# Adafruit_Feather_M4_Express_CAN.net
KiCad netlist of a schematic drawn in EAGLE
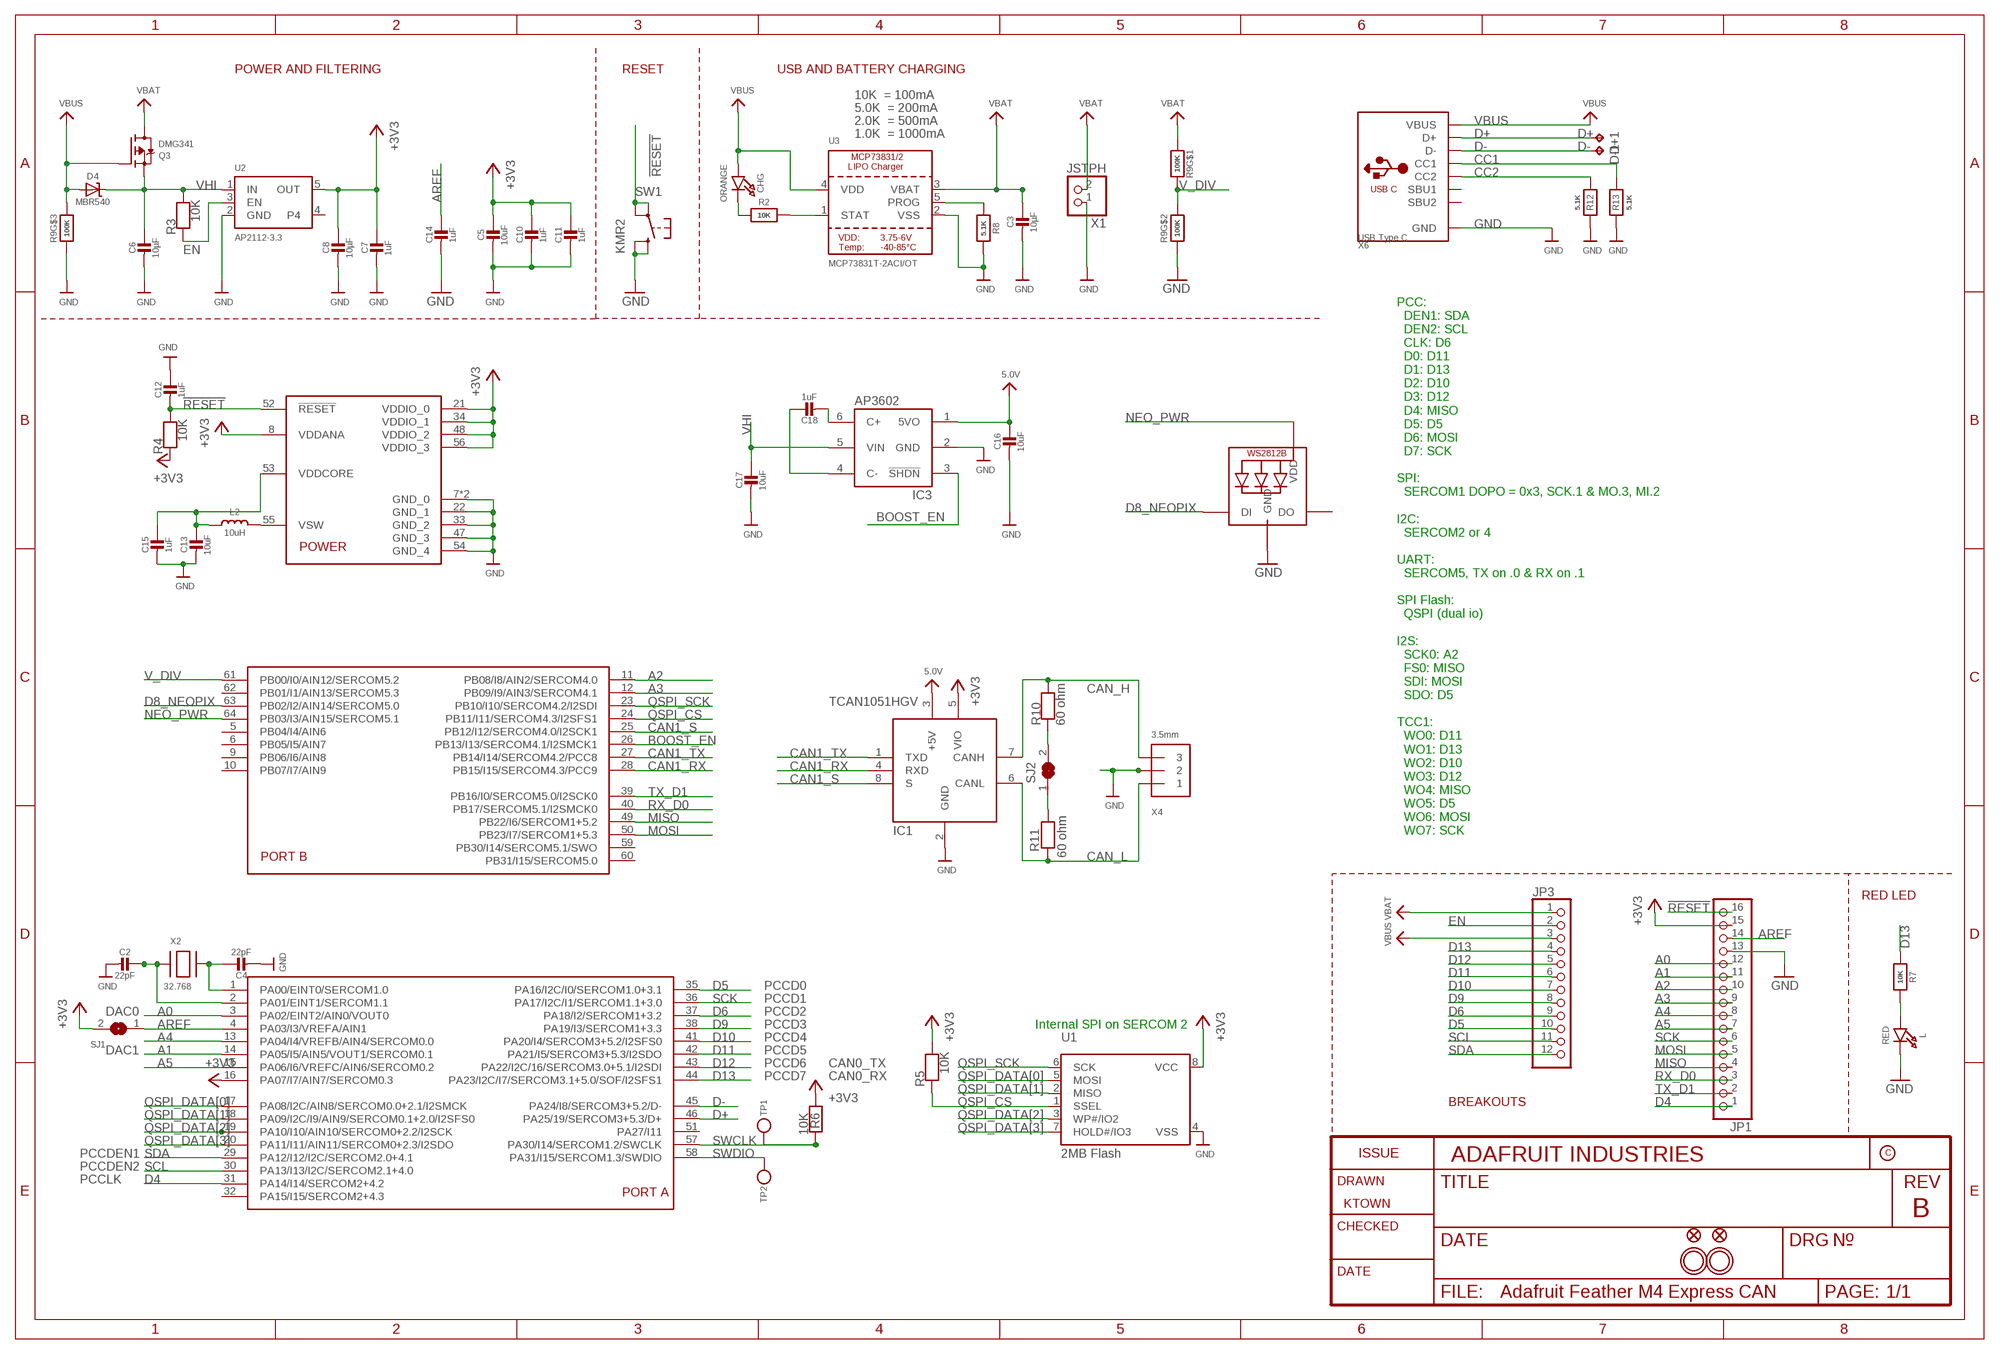
[diagram p0: schematic, sheet 1]

(export (version "E")
  (design (tool "Eeschema 10.0.6"))
  (components
    (comp (ref "C2")
      (value "22pF")
      (footprint "eagle-import:0603-NO")
      (libsource (lib "eagle-import") (part "CAP_CERAMIC0603_NO"))
    )
    (comp (ref "C3")
      (value "10µF")
      (footprint "eagle-import:0805-NO")
      (libsource (lib "eagle-import") (part "CAP_CERAMIC0805-NOOUTLINE"))
    )
    (comp (ref "C4")
      (value "22pF")
      (footprint "eagle-import:0603-NO")
      (libsource (lib "eagle-import") (part "CAP_CERAMIC0603_NO"))
    )
    (comp (ref "C5")
      (value "10uF")
      (footprint "eagle-import:0805-NO")
      (libsource (lib "eagle-import") (part "CAP_CERAMIC0805-NOOUTLINE"))
    )
    (comp (ref "C6")
      (value "10µF")
      (footprint "eagle-import:0805-NO")
      (libsource (lib "eagle-import") (part "CAP_CERAMIC0805-NOOUTLINE"))
    )
    (comp (ref "C7")
      (value "1uF")
      (footprint "eagle-import:0603-NO")
      (libsource (lib "eagle-import") (part "CAP_CERAMIC0603_NO"))
    )
    (comp (ref "C8")
      (value "10µF")
      (footprint "eagle-import:0805-NO")
      (fields (field (name "REV") "C"))
      (libsource (lib "eagle-import") (part "CAP_CERAMIC0805-NOOUTLINE"))
    )
    (comp (ref "C10")
      (value "1uF")
      (footprint "eagle-import:0603-NO")
      (libsource (lib "eagle-import") (part "CAP_CERAMIC0603_NO"))
    )
    (comp (ref "C11")
      (value "1uF")
      (footprint "eagle-import:0603-NO")
      (libsource (lib "eagle-import") (part "CAP_CERAMIC0603_NO"))
    )
    (comp (ref "C12")
      (value "1uF")
      (footprint "eagle-import:0603-NO")
      (libsource (lib "eagle-import") (part "CAP_CERAMIC0603_NO"))
    )
    (comp (ref "C13")
      (value "10uF")
      (footprint "eagle-import:0805-NO")
      (libsource (lib "eagle-import") (part "CAP_CERAMIC0805-NOOUTLINE"))
    )
    (comp (ref "C14")
      (value "1uF")
      (footprint "eagle-import:0603-NO")
      (libsource (lib "eagle-import") (part "CAP_CERAMIC0603_NO"))
    )
    (comp (ref "C15")
      (value "1uF")
      (footprint "eagle-import:0603-NO")
      (libsource (lib "eagle-import") (part "CAP_CERAMIC0603_NO"))
    )
    (comp (ref "C16")
      (value "10uF")
      (footprint "eagle-import:_0805MP")
      (libsource (lib "eagle-import") (part "CAP_CERAMIC_0805MP"))
    )
    (comp (ref "C17")
      (value "10uF")
      (footprint "eagle-import:0805-NO")
      (libsource (lib "eagle-import") (part "CAP_CERAMIC0805-NOOUTLINE"))
    )
    (comp (ref "C18")
      (value "1uF")
      (footprint "eagle-import:0805_10MGAP")
      (libsource (lib "eagle-import") (part "CAP_CERAMIC0805_10MGAP"))
    )
    (comp (ref "CHG")
      (value "ORANGE")
      (footprint "eagle-import:CHIPLED_0603_NOOUTLINE")
      (libsource (lib "eagle-import") (part "LED0603_NOOUTLINE"))
    )
    (comp (ref "D+1")
      (value "TPB1,27")
      (footprint "eagle-import:B1,27")
      (libsource (lib "eagle-import") (part "TPB1,27"))
    )
    (comp (ref "D-1")
      (value "TPB1,27")
      (footprint "eagle-import:B1,27")
      (libsource (lib "eagle-import") (part "TPB1,27"))
    )
    (comp (ref "D4")
      (value "MBR540")
      (footprint "eagle-import:SOD-123")
      (libsource (lib "eagle-import") (part "DIODE-SCHOTTKYSOD-123"))
    )
    (comp (ref "IC1")
      (value "TCAN1051HGV")
      (footprint "eagle-import:SOIC8_150MIL")
      (libsource (lib "eagle-import") (part "CAN_TRANSCIEVER_TCAN1051V"))
    )
    (comp (ref "IC3")
      (value "AP3602")
      (footprint "eagle-import:SOT23-6")
      (libsource (lib "eagle-import") (part "AP3602"))
    )
    (comp (ref "JP1")
      (value "HEADER-1X16ROUND")
      (footprint "eagle-import:1X16_ROUND")
      (libsource (lib "eagle-import") (part "HEADER-1X16ROUND"))
    )
    (comp (ref "JP3")
      (value "HEADER-1X12")
      (footprint "eagle-import:1X12_ROUND")
      (libsource (lib "eagle-import") (part "HEADER-1X12"))
    )
    (comp (ref "L")
      (value "RED")
      (footprint "eagle-import:CHIPLED_0603_NOOUTLINE")
      (libsource (lib "eagle-import") (part "LED0603_NOOUTLINE"))
    )
    (comp (ref "L2")
      (value "10uH")
      (footprint "eagle-import:INDUCTOR_1007")
      (libsource (lib "eagle-import") (part "INDUCTOR"))
    )
    (comp (ref "LED1")
      (value "WS2812B3535")
      (footprint "eagle-import:LED3535")
      (libsource (lib "eagle-import") (part "WS2812B3535"))
    )
    (comp (ref "Q3")
      (value "DMG341")
      (footprint "eagle-import:SOT23-R")
      (libsource (lib "eagle-import") (part "MOSFET-P"))
    )
    (comp (ref "R2")
      (value "10K")
      (footprint "eagle-import:0603-NO")
      (libsource (lib "eagle-import") (part "RESISTOR_0603_NOOUT"))
    )
    (comp (ref "R3")
      (value "10K")
      (footprint "eagle-import:0603-NO")
      (libsource (lib "eagle-import") (part "RESISTOR_0603_NOOUT"))
    )
    (comp (ref "R4")
      (value "10K")
      (footprint "eagle-import:0603-NO")
      (libsource (lib "eagle-import") (part "RESISTOR_0603_NOOUT"))
    )
    (comp (ref "R5")
      (value "10K")
      (footprint "eagle-import:0603-NO")
      (libsource (lib "eagle-import") (part "RESISTOR_0603_NOOUT"))
    )
    (comp (ref "R6")
      (value "10K")
      (footprint "eagle-import:0603-NO")
      (libsource (lib "eagle-import") (part "RESISTOR_0603_NOOUT"))
    )
    (comp (ref "R7")
      (value "10K")
      (footprint "eagle-import:0603-NO")
      (libsource (lib "eagle-import") (part "RESISTOR_0603_NOOUT"))
    )
    (comp (ref "R8")
      (value "5.1K")
      (footprint "eagle-import:0603-NO")
      (libsource (lib "eagle-import") (part "RESISTOR_0603_NOOUT"))
    )
    (comp (ref "R9")
      (value "100K")
      (footprint "eagle-import:RESPACK_4X0603_NO")
      (libsource (lib "eagle-import") (part "RESISTOR_4PACK_NO"))
    )
    (comp (ref "R10")
      (value "60 ohm")
      (footprint "eagle-import:0805-NO")
      (libsource (lib "eagle-import") (part "RESISTOR0805_NOOUTLINE"))
    )
    (comp (ref "R11")
      (value "60 ohm")
      (footprint "eagle-import:0805-NO")
      (libsource (lib "eagle-import") (part "RESISTOR0805_NOOUTLINE"))
    )
    (comp (ref "R12")
      (value "5.1K")
      (footprint "eagle-import:0603-NO")
      (libsource (lib "eagle-import") (part "RESISTOR_0603_NOOUT"))
    )
    (comp (ref "R13")
      (value "5.1K")
      (footprint "eagle-import:0603-NO")
      (libsource (lib "eagle-import") (part "RESISTOR_0603_NOOUT"))
    )
    (comp (ref "SJ1")
      (value "SOLDERJUMPERCLOSED")
      (footprint "eagle-import:SOLDERJUMPER_CLOSEDWIRE")
      (libsource (lib "eagle-import") (part "SOLDERJUMPERCLOSED"))
    )
    (comp (ref "SJ2")
      (value "SOLDERJUMPER_CLOSED")
      (footprint "eagle-import:SOLDERJUMPER_CLOSEDWIRE")
      (libsource (lib "eagle-import") (part "SOLDERJUMPER_CLOSED"))
    )
    (comp (ref "SW1")
      (value "KMR2")
      (footprint "eagle-import:BTN_KMR2_4.6X2.8")
      (libsource (lib "eagle-import") (part "SWITCH_TACT_SMT4.6X2.8"))
    )
    (comp (ref "TP1")
      (value "TESTPOINTROUND1.5MM")
      (footprint "eagle-import:TESTPOINT_ROUND_1.5MM")
      (libsource (lib "eagle-import") (part "TESTPOINTROUND1.5MM"))
    )
    (comp (ref "TP2")
      (value "TESTPOINTROUND1.5MM")
      (footprint "eagle-import:TESTPOINT_ROUND_1.5MM")
      (libsource (lib "eagle-import") (part "TESTPOINTROUND1.5MM"))
    )
    (comp (ref "U$14")
      (value "ATSAMD51J")
      (footprint "eagle-import:PQFN64-1")
      (libsource (lib "eagle-import") (part "ATSAMD51J"))
    )
    (comp (ref "U$31")
      (value "MOUNTINGHOLE2.5")
      (footprint "eagle-import:MOUNTINGHOLE_2.5_PLATED")
      (libsource (lib "eagle-import") (part "MOUNTINGHOLE2.5"))
    )
    (comp (ref "U$32")
      (value "MOUNTINGHOLE2.5")
      (footprint "eagle-import:MOUNTINGHOLE_2.5_PLATED")
      (libsource (lib "eagle-import") (part "MOUNTINGHOLE2.5"))
    )
    (comp (ref "U$34")
      (value "FIDUCIAL_1MM")
      (footprint "eagle-import:FIDUCIAL_1MM")
      (libsource (lib "eagle-import") (part "FIDUCIAL_1MM"))
    )
    (comp (ref "U$35")
      (value "FIDUCIAL_1MM")
      (footprint "eagle-import:FIDUCIAL_1MM")
      (libsource (lib "eagle-import") (part "FIDUCIAL_1MM"))
    )
    (comp (ref "U1")
      (value "2MB Flash")
      (footprint "eagle-import:USON8")
      (libsource (lib "eagle-import") (part "SPIFLASH_8PINUX"))
    )
    (comp (ref "U2")
      (value "AP2112-3.3")
      (footprint "eagle-import:SOT23-5@1")
      (libsource (lib "eagle-import") (part "VREG_SOT23-5"))
    )
    (comp (ref "U3")
      (value "MCP73831T-2ACI/OT")
      (footprint "eagle-import:SOT23-5")
      (libsource (lib "eagle-import") (part "MCP73831/2"))
    )
    (comp (ref "X1")
      (value "JSTPH")
      (footprint "eagle-import:JSTPH2_BATT")
      (libsource (lib "eagle-import") (part "CON_JST_PH_2PIN_BATT"))
    )
    (comp (ref "X2")
      (value "32.768")
      (footprint "eagle-import:XTAL3215")
      (libsource (lib "eagle-import") (part "XTAL-3.2X1.5"))
    )
    (comp (ref "X4")
      (value "3.5mm")
      (footprint "eagle-import:TERMBLOCK_1X3-3.5MM")
      (libsource (lib "eagle-import") (part "TERMBLOCK_1X3"))
    )
    (comp (ref "X6")
      (value "USB Type C")
      (footprint "eagle-import:USB_C_CUSB31-CFM2AX-01-X")
      (libsource (lib "eagle-import") (part "USB_C"))
    )
  )
  (nets
    (net (code "1") (name "+3V3") (class "Default")
      (node (ref "C10") (pin "1") (pinfunction "1_1") (pintype "passive"))
      (node (ref "C11") (pin "1") (pinfunction "1_1") (pintype "passive"))
      (node (ref "C5") (pin "1") (pinfunction "1_1") (pintype "passive"))
      (node (ref "C7") (pin "1") (pinfunction "1_1") (pintype "passive"))
      (node (ref "C8") (pin "1") (pinfunction "1_1") (pintype "passive"))
      (node (ref "IC1") (pin "5") (pinfunction "VIO_5") (pintype "power_in"))
      (node (ref "JP1") (pin "15") (pinfunction "15_15") (pintype "passive"))
      (node (ref "R4") (pin "1") (pinfunction "1_1") (pintype "passive"))
      (node (ref "R5") (pin "2") (pinfunction "2_2") (pintype "passive"))
      (node (ref "R6") (pin "1") (pinfunction "1_1") (pintype "passive"))
      (node (ref "SJ1") (pin "2") (pinfunction "2_2") (pintype "passive"))
      (node (ref "U$14") (pin "16") (pinfunction "PA07/I7/AIN7/SERCOM0.3_16") (pintype "bidirectional"))
      (node (ref "U$14") (pin "21") (pinfunction "VDDIO_0_21") (pintype "bidirectional"))
      (node (ref "U$14") (pin "34") (pinfunction "VDDIO_1_34") (pintype "bidirectional"))
      (node (ref "U$14") (pin "48") (pinfunction "VDDIO_2_48") (pintype "bidirectional"))
      (node (ref "U$14") (pin "56") (pinfunction "VDDIO_3_56") (pintype "bidirectional"))
      (node (ref "U$14") (pin "8") (pinfunction "VDDANA_8") (pintype "bidirectional"))
      (node (ref "U1") (pin "8") (pinfunction "VCC_8") (pintype "bidirectional"))
      (node (ref "U2") (pin "5") (pinfunction "OUT_5") (pintype "power_in"))
    )
    (net (code "2") (name "/A0") (class "Default")
      (node (ref "JP1") (pin "12") (pinfunction "12_12") (pintype "passive"))
      (node (ref "U$14") (pin "3") (pinfunction "PA02/EINT2/AIN0/VOUT0_3") (pintype "bidirectional"))
    )
    (net (code "3") (name "/A1") (class "Default")
      (node (ref "JP1") (pin "11") (pinfunction "11_11") (pintype "passive"))
      (node (ref "U$14") (pin "14") (pinfunction "PA05/I5/AIN5/VOUT1/SERCOM0.1_14") (pintype "bidirectional"))
    )
    (net (code "4") (name "/A2") (class "Default")
      (node (ref "JP1") (pin "10") (pinfunction "10_10") (pintype "passive"))
      (node (ref "U$14") (pin "11") (pinfunction "PB08/I8/AIN2/SERCOM4.0_11") (pintype "bidirectional"))
    )
    (net (code "5") (name "/A3") (class "Default")
      (node (ref "JP1") (pin "9") (pinfunction "9_9") (pintype "passive"))
      (node (ref "U$14") (pin "12") (pinfunction "PB09/I9/AIN3/SERCOM4.1_12") (pintype "bidirectional"))
    )
    (net (code "6") (name "/A4") (class "Default")
      (node (ref "JP1") (pin "8") (pinfunction "8_8") (pintype "passive"))
      (node (ref "U$14") (pin "13") (pinfunction "PA04/I4/VREFB/AIN4/SERCOM0.0_13") (pintype "bidirectional"))
    )
    (net (code "7") (name "/A5") (class "Default")
      (node (ref "JP1") (pin "7") (pinfunction "7_7") (pintype "passive"))
      (node (ref "U$14") (pin "15") (pinfunction "PA06/I6/VREFC/AIN6/SERCOM0.2_15") (pintype "bidirectional"))
    )
    (net (code "8") (name "/AREF") (class "Default")
      (node (ref "C14") (pin "1") (pinfunction "1_1") (pintype "passive"))
      (node (ref "JP1") (pin "14") (pinfunction "14_14") (pintype "passive"))
      (node (ref "SJ1") (pin "1") (pinfunction "1_1") (pintype "passive"))
      (node (ref "U$14") (pin "4") (pinfunction "PA03/I3/VREFA/AIN1_4") (pintype "bidirectional"))
    )
    (net (code "9") (name "/BOOST_EN") (class "Default")
      (node (ref "IC3") (pin "3") (pinfunction "~{SHDN}_3") (pintype "input"))
      (node (ref "U$14") (pin "26") (pinfunction "PB13/I13/SERCOM4.1/I2SMCK1_26") (pintype "bidirectional"))
    )
    (net (code "10") (name "/CAN1_RX") (class "Default")
      (node (ref "IC1") (pin "4") (pinfunction "RXD_4") (pintype "output"))
      (node (ref "U$14") (pin "28") (pinfunction "PB15/I15/SERCOM4.3/PCC9_28") (pintype "bidirectional"))
    )
    (net (code "11") (name "/CAN1_S") (class "Default")
      (node (ref "IC1") (pin "8") (pinfunction "S_8") (pintype "input"))
      (node (ref "U$14") (pin "25") (pinfunction "PB12/I12/SERCOM4.0/I2SCK1_25") (pintype "bidirectional"))
    )
    (net (code "12") (name "/CAN1_TX") (class "Default")
      (node (ref "IC1") (pin "1") (pinfunction "TXD_1") (pintype "input"))
      (node (ref "U$14") (pin "27") (pinfunction "PB14/I14/SERCOM4.2/PCC8_27") (pintype "bidirectional"))
    )
    (net (code "13") (name "/CAN_H") (class "Default")
      (node (ref "IC1") (pin "7") (pinfunction "CANH_7") (pintype "bidirectional"))
      (node (ref "R10") (pin "2") (pinfunction "2_2") (pintype "passive"))
      (node (ref "X4") (pin "3") (pinfunction "3_3") (pintype "passive"))
    )
    (net (code "14") (name "/CAN_L") (class "Default")
      (node (ref "IC1") (pin "6") (pinfunction "CANL_6") (pintype "bidirectional"))
      (node (ref "R11") (pin "2") (pinfunction "2_2") (pintype "passive"))
      (node (ref "X4") (pin "1") (pinfunction "1_1") (pintype "passive"))
    )
    (net (code "15") (name "/CC1") (class "Default")
      (node (ref "R13") (pin "2") (pinfunction "2_2") (pintype "passive"))
      (node (ref "X6") (pin "A5") (pinfunction "CC1_A5") (pintype "bidirectional"))
    )
    (net (code "16") (name "/CC2") (class "Default")
      (node (ref "R12") (pin "2") (pinfunction "2_2") (pintype "passive"))
      (node (ref "X6") (pin "B5") (pinfunction "CC2_B5") (pintype "bidirectional"))
    )
    (net (code "17") (name "/D+") (class "Default")
      (node (ref "D+1") (pin "TP") (pinfunction "TP_TP") (pintype "input"))
      (node (ref "U$14") (pin "46") (pinfunction "PA25/19/SERCOM3+5.3/D+_46") (pintype "bidirectional"))
      (node (ref "X6") (pin "A6") (pinfunction "D+_A6") (pintype "bidirectional"))
      (node (ref "X6") (pin "B6") (pinfunction "D+_B6") (pintype "bidirectional"))
    )
    (net (code "18") (name "/D-") (class "Default")
      (node (ref "D-1") (pin "TP") (pinfunction "TP_TP") (pintype "input"))
      (node (ref "U$14") (pin "45") (pinfunction "PA24/I8/SERCOM3+5.2/D-_45") (pintype "bidirectional"))
      (node (ref "X6") (pin "A7") (pinfunction "D-_A7") (pintype "bidirectional"))
      (node (ref "X6") (pin "B7") (pinfunction "D-_B7") (pintype "bidirectional"))
    )
    (net (code "19") (name "/D4") (class "Default")
      (node (ref "JP1") (pin "1") (pinfunction "1_1") (pintype "passive"))
      (node (ref "U$14") (pin "31") (pinfunction "PA14/I14/SERCOM2+4.2_31") (pintype "bidirectional"))
    )
    (net (code "20") (name "/D5") (class "Default")
      (node (ref "JP3") (pin "10") (pinfunction "10_10") (pintype "passive"))
      (node (ref "U$14") (pin "35") (pinfunction "PA16/I2C/I0/SERCOM1.0+3.1_35") (pintype "bidirectional"))
    )
    (net (code "21") (name "/D6") (class "Default")
      (node (ref "JP3") (pin "9") (pinfunction "9_9") (pintype "passive"))
      (node (ref "U$14") (pin "37") (pinfunction "PA18/I2/SERCOM1+3.2_37") (pintype "bidirectional"))
    )
    (net (code "22") (name "/D8_NEOPIX") (class "Default")
      (node (ref "LED1") (pin "1") (pinfunction "DI_1") (pintype "input"))
      (node (ref "U$14") (pin "63") (pinfunction "PB02/I2/AIN14/SERCOM5.0_63") (pintype "bidirectional"))
    )
    (net (code "23") (name "/D9") (class "Default")
      (node (ref "JP3") (pin "8") (pinfunction "8_8") (pintype "passive"))
      (node (ref "U$14") (pin "38") (pinfunction "PA19/I3/SERCOM1+3.3_38") (pintype "bidirectional"))
    )
    (net (code "24") (name "/D10") (class "Default")
      (node (ref "JP3") (pin "7") (pinfunction "7_7") (pintype "passive"))
      (node (ref "U$14") (pin "41") (pinfunction "PA20/I4/SERCOM3+5.2/I2SFS0_41") (pintype "bidirectional"))
    )
    (net (code "25") (name "/D11") (class "Default")
      (node (ref "JP3") (pin "6") (pinfunction "6_6") (pintype "passive"))
      (node (ref "U$14") (pin "42") (pinfunction "PA21/I5/SERCOM3+5.3/I2SDO_42") (pintype "bidirectional"))
    )
    (net (code "26") (name "/D12") (class "Default")
      (node (ref "JP3") (pin "5") (pinfunction "5_5") (pintype "passive"))
      (node (ref "U$14") (pin "43") (pinfunction "PA22/I2C/16/SERCOM3.0+5.1/I2SDI_43") (pintype "bidirectional"))
    )
    (net (code "27") (name "/D13") (class "Default")
      (node (ref "JP3") (pin "4") (pinfunction "4_4") (pintype "passive"))
      (node (ref "R7") (pin "1") (pinfunction "1_1") (pintype "passive"))
      (node (ref "U$14") (pin "44") (pinfunction "PA23/I2C/I7/SERCOM3.1+5.0/SOF/I2SFS1_44") (pintype "bidirectional"))
    )
    (net (code "28") (name "/EN") (class "Default")
      (node (ref "JP3") (pin "2") (pinfunction "2_2") (pintype "passive"))
      (node (ref "R3") (pin "1") (pinfunction "1_1") (pintype "passive"))
      (node (ref "U2") (pin "3") (pinfunction "EN_3") (pintype "input"))
    )
    (net (code "29") (name "/MISO") (class "Default")
      (node (ref "JP1") (pin "4") (pinfunction "4_4") (pintype "passive"))
      (node (ref "U$14") (pin "49") (pinfunction "PB22/I6/SERCOM1+5.2_49") (pintype "bidirectional"))
    )
    (net (code "30") (name "/MOSI") (class "Default")
      (node (ref "JP1") (pin "5") (pinfunction "5_5") (pintype "passive"))
      (node (ref "U$14") (pin "50") (pinfunction "PB23/I7/SERCOM1+5.3_50") (pintype "bidirectional"))
    )
    (net (code "31") (name "/NEO_PWR") (class "Default")
      (node (ref "LED1") (pin "2") (pinfunction "VDD_2") (pintype "power_in"))
      (node (ref "U$14") (pin "64") (pinfunction "PB03/I3/AIN15/SERCOM5.1_64") (pintype "bidirectional"))
    )
    (net (code "32") (name "/QSPI_CS") (class "Default")
      (node (ref "R5") (pin "1") (pinfunction "1_1") (pintype "passive"))
      (node (ref "U$14") (pin "24") (pinfunction "PB11/I11/SERCOM4.3/I2SFS1_24") (pintype "bidirectional"))
      (node (ref "U1") (pin "1") (pinfunction "SSEL_1") (pintype "bidirectional"))
    )
    (net (code "33") (name "/QSPI_DATA[0]") (class "Default")
      (node (ref "U$14") (pin "17") (pinfunction "PA08/I2C/AIN8/SERCOM0.0+2.1/I2SMCK_17") (pintype "bidirectional"))
      (node (ref "U1") (pin "5") (pinfunction "MOSI_5") (pintype "bidirectional"))
    )
    (net (code "34") (name "/QSPI_DATA[1]") (class "Default")
      (node (ref "U$14") (pin "18") (pinfunction "PA09/I2C/I9/AIN9/SERCOM0.1+2.0/I2SFS0_18") (pintype "bidirectional"))
      (node (ref "U1") (pin "2") (pinfunction "MISO_2") (pintype "bidirectional"))
    )
    (net (code "35") (name "/QSPI_DATA[2]") (class "Default")
      (node (ref "U$14") (pin "19") (pinfunction "PA10/I10/AIN10/SERCOM0+2.2/I2SCK_19") (pintype "bidirectional"))
      (node (ref "U1") (pin "3") (pinfunction "WP#/IO2_3") (pintype "bidirectional"))
    )
    (net (code "36") (name "/QSPI_DATA[3]") (class "Default")
      (node (ref "U$14") (pin "20") (pinfunction "PA11/I11/AIN11/SERCOM0+2.3/I2SDO_20") (pintype "bidirectional"))
      (node (ref "U1") (pin "7") (pinfunction "HOLD#/IO3_7") (pintype "bidirectional"))
    )
    (net (code "37") (name "/QSPI_SCK") (class "Default")
      (node (ref "U$14") (pin "23") (pinfunction "PB10/I10/SERCOM4.2/I2SDI_23") (pintype "bidirectional"))
      (node (ref "U1") (pin "6") (pinfunction "SCK_6") (pintype "bidirectional"))
    )
    (net (code "38") (name "/RX_D0") (class "Default")
      (node (ref "JP1") (pin "3") (pinfunction "3_3") (pintype "passive"))
      (node (ref "U$14") (pin "40") (pinfunction "PB17/SERCOM5.1/I2SMCK0_40") (pintype "bidirectional"))
    )
    (net (code "39") (name "/SCK") (class "Default")
      (node (ref "JP1") (pin "6") (pinfunction "6_6") (pintype "passive"))
      (node (ref "U$14") (pin "36") (pinfunction "PA17/I2C/I1/SERCOM1.1+3.0_36") (pintype "bidirectional"))
    )
    (net (code "40") (name "/SCL") (class "Default")
      (node (ref "JP3") (pin "11") (pinfunction "11_11") (pintype "passive"))
      (node (ref "U$14") (pin "30") (pinfunction "PA13/I13/I2C/SERCOM2.1+4.0_30") (pintype "bidirectional"))
    )
    (net (code "41") (name "/SDA") (class "Default")
      (node (ref "JP3") (pin "12") (pinfunction "12_12") (pintype "passive"))
      (node (ref "U$14") (pin "29") (pinfunction "PA12/I12/I2C/SERCOM2.0+4.1_29") (pintype "bidirectional"))
    )
    (net (code "42") (name "/SWCLK") (class "Default")
      (node (ref "R6") (pin "2") (pinfunction "2_2") (pintype "passive"))
      (node (ref "TP1") (pin "P$1") (pinfunction "P$1_P$1") (pintype "bidirectional"))
      (node (ref "U$14") (pin "57") (pinfunction "PA30/I14/SERCOM1.2/SWCLK_57") (pintype "bidirectional"))
    )
    (net (code "43") (name "/SWDIO") (class "Default")
      (node (ref "TP2") (pin "P$1") (pinfunction "P$1_P$1") (pintype "bidirectional"))
      (node (ref "U$14") (pin "58") (pinfunction "PA31/I15/SERCOM1.3/SWDIO_58") (pintype "bidirectional"))
    )
    (net (code "44") (name "/TX_D1") (class "Default")
      (node (ref "JP1") (pin "2") (pinfunction "2_2") (pintype "passive"))
      (node (ref "U$14") (pin "39") (pinfunction "PB16/I0/SERCOM5.0/I2SCK0_39") (pintype "bidirectional"))
    )
    (net (code "45") (name "/VHI") (class "Default")
      (node (ref "C17") (pin "1") (pinfunction "1_1") (pintype "passive"))
      (node (ref "C6") (pin "1") (pinfunction "1_1") (pintype "passive"))
      (node (ref "D4") (pin "C") (pinfunction "C_C") (pintype "passive"))
      (node (ref "IC3") (pin "5") (pinfunction "VIN_5") (pintype "power_in"))
      (node (ref "Q3") (pin "2") (pinfunction "S_2") (pintype "passive"))
      (node (ref "R3") (pin "2") (pinfunction "2_2") (pintype "passive"))
      (node (ref "U2") (pin "1") (pinfunction "IN_1") (pintype "power_in"))
    )
    (net (code "46") (name "/V_DIV") (class "Default")
      (node (ref "R9") (pin "1") (pinfunction "1_1") (pintype "passive"))
      (node (ref "R9") (pin "2") (pinfunction "1_2") (pintype "passive"))
      (node (ref "U$14") (pin "61") (pinfunction "PB00/I0/AIN12/SERCOM5.2_61") (pintype "bidirectional"))
    )
    (net (code "47") (name "/~{RESET}") (class "Default")
      (node (ref "C12") (pin "2") (pinfunction "2_2") (pintype "passive"))
      (node (ref "JP1") (pin "16") (pinfunction "16_16") (pintype "passive"))
      (node (ref "R4") (pin "2") (pinfunction "2_2") (pintype "passive"))
      (node (ref "SW1") (pin "A") (pinfunction "P_A") (pintype "passive"))
      (node (ref "SW1") (pin "A'") (pinfunction "P1_A'") (pintype "passive"))
      (node (ref "U$14") (pin "52") (pinfunction "~{RESET}_52") (pintype "bidirectional"))
    )
    (net (code "48") (name "5.0V") (class "Default")
      (node (ref "C16") (pin "1") (pinfunction "1_1") (pintype "passive"))
      (node (ref "IC1") (pin "3") (pinfunction "+5V_3") (pintype "power_in"))
      (node (ref "IC3") (pin "1") (pinfunction "5VO_1") (pintype "power_in"))
    )
    (net (code "49") (name "GND") (class "Default")
      (node (ref "C10") (pin "2") (pinfunction "2_2") (pintype "passive"))
      (node (ref "C11") (pin "2") (pinfunction "2_2") (pintype "passive"))
      (node (ref "C12") (pin "1") (pinfunction "1_1") (pintype "passive"))
      (node (ref "C13") (pin "2") (pinfunction "2_2") (pintype "passive"))
      (node (ref "C14") (pin "2") (pinfunction "2_2") (pintype "passive"))
      (node (ref "C15") (pin "2") (pinfunction "2_2") (pintype "passive"))
      (node (ref "C16") (pin "2") (pinfunction "2_2") (pintype "passive"))
      (node (ref "C17") (pin "2") (pinfunction "2_2") (pintype "passive"))
      (node (ref "C2") (pin "2") (pinfunction "2_2") (pintype "passive"))
      (node (ref "C3") (pin "2") (pinfunction "2_2") (pintype "passive"))
      (node (ref "C4") (pin "2") (pinfunction "2_2") (pintype "passive"))
      (node (ref "C5") (pin "2") (pinfunction "2_2") (pintype "passive"))
      (node (ref "C6") (pin "2") (pinfunction "2_2") (pintype "passive"))
      (node (ref "C7") (pin "2") (pinfunction "2_2") (pintype "passive"))
      (node (ref "C8") (pin "2") (pinfunction "2_2") (pintype "passive"))
      (node (ref "IC1") (pin "2") (pinfunction "GND_2") (pintype "power_in"))
      (node (ref "IC3") (pin "2") (pinfunction "GND_2") (pintype "power_in"))
      (node (ref "JP1") (pin "13") (pinfunction "13_13") (pintype "passive"))
      (node (ref "L") (pin "C") (pinfunction "C_C") (pintype "passive"))
      (node (ref "LED1") (pin "4") (pinfunction "GND_4") (pintype "power_in"))
      (node (ref "R12") (pin "1") (pinfunction "1_1") (pintype "passive"))
      (node (ref "R13") (pin "1") (pinfunction "1_1") (pintype "passive"))
      (node (ref "R8") (pin "2") (pinfunction "2_2") (pintype "passive"))
      (node (ref "R9") (pin "3") (pinfunction "1_3") (pintype "passive"))
      (node (ref "R9") (pin "7") (pinfunction "2_7") (pintype "passive"))
      (node (ref "SW1") (pin "B") (pinfunction "S_B") (pintype "passive"))
      (node (ref "SW1") (pin "B'") (pinfunction "S1_B'") (pintype "passive"))
      (node (ref "U$14") (pin "22") (pinfunction "GND_1_22") (pintype "bidirectional"))
      (node (ref "U$14") (pin "33") (pinfunction "GND_2_33") (pintype "bidirectional"))
      (node (ref "U$14") (pin "47") (pinfunction "GND_3_47") (pintype "bidirectional"))
      (node (ref "U$14") (pin "54") (pinfunction "GND_4_54") (pintype "bidirectional"))
      (node (ref "U$14") (pin "7") (pinfunction "GND_0_7") (pintype "bidirectional"))
      (node (ref "U$14") (pin "EXP") (pinfunction "GND_0_EXP") (pintype "bidirectional"))
      (node (ref "U1") (pin "4") (pinfunction "VSS_4") (pintype "bidirectional"))
      (node (ref "U2") (pin "2") (pinfunction "GND_2") (pintype "power_in"))
      (node (ref "U3") (pin "2") (pinfunction "VSS_2") (pintype "power_in"))
      (node (ref "X1") (pin "1") (pinfunction "1_1") (pintype "passive"))
      (node (ref "X4") (pin "2") (pinfunction "2_2") (pintype "passive"))
      (node (ref "X6") (pin "A1B12") (pinfunction "GND_A1B12") (pintype "power_in"))
      (node (ref "X6") (pin "B1A12") (pinfunction "GND_B1A12") (pintype "power_in"))
    )
    (net (code "50") (name "Net-(CHG-PadC)") (class "Default")
      (node (ref "CHG") (pin "C") (pinfunction "C_C") (pintype "passive"))
      (node (ref "R2") (pin "1") (pinfunction "1_1") (pintype "passive"))
    )
    (net (code "51") (name "Net-(IC3-C+)") (class "Default")
      (node (ref "C18") (pin "2") (pinfunction "2_2") (pintype "passive"))
      (node (ref "IC3") (pin "6") (pinfunction "C+_6") (pintype "bidirectional"))
    )
    (net (code "52") (name "Net-(IC3-C-)") (class "Default")
      (node (ref "C18") (pin "1") (pinfunction "1_1") (pintype "passive"))
      (node (ref "IC3") (pin "4") (pinfunction "C-_4") (pintype "bidirectional"))
    )
    (net (code "53") (name "Net-(L-PadA)") (class "Default")
      (node (ref "L") (pin "A") (pinfunction "A_A") (pintype "passive"))
      (node (ref "R7") (pin "2") (pinfunction "2_2") (pintype "passive"))
    )
    (net (code "54") (name "Net-(L2-1)") (class "Default")
      (node (ref "C13") (pin "1") (pinfunction "1_1") (pintype "passive"))
      (node (ref "C15") (pin "1") (pinfunction "1_1") (pintype "passive"))
      (node (ref "L2") (pin "P$1") (pinfunction "1_P$1") (pintype "passive"))
      (node (ref "U$14") (pin "53") (pinfunction "VDDCORE_53") (pintype "bidirectional"))
    )
    (net (code "55") (name "Net-(L2-2)") (class "Default")
      (node (ref "L2") (pin "P$2") (pinfunction "2_P$2") (pintype "passive"))
      (node (ref "U$14") (pin "55") (pinfunction "VSW_55") (pintype "bidirectional"))
    )
    (net (code "56") (name "Net-(R10-Pad1)") (class "Default")
      (node (ref "R10") (pin "1") (pinfunction "1_1") (pintype "passive"))
      (node (ref "SJ2") (pin "2") (pinfunction "2_2") (pintype "passive"))
    )
    (net (code "57") (name "Net-(R11-Pad1)") (class "Default")
      (node (ref "R11") (pin "1") (pinfunction "1_1") (pintype "passive"))
      (node (ref "SJ2") (pin "1") (pinfunction "1_1") (pintype "passive"))
    )
    (net (code "58") (name "Net-(U$14A-PA00{slash}EINT0{slash}SERCOM1.0)") (class "Default")
      (node (ref "C4") (pin "1") (pinfunction "1_1") (pintype "passive"))
      (node (ref "U$14") (pin "1") (pinfunction "PA00/EINT0/SERCOM1.0_1") (pintype "bidirectional"))
      (node (ref "X2") (pin "P$2") (pinfunction "P$2_P$2") (pintype "bidirectional"))
    )
    (net (code "59") (name "Net-(U$14A-PA01{slash}EINT1{slash}SERCOM1.1)") (class "Default")
      (node (ref "C2") (pin "1") (pinfunction "1_1") (pintype "passive"))
      (node (ref "U$14") (pin "2") (pinfunction "PA01/EINT1/SERCOM1.1_2") (pintype "bidirectional"))
      (node (ref "X2") (pin "P$1") (pinfunction "P$1_P$1") (pintype "bidirectional"))
    )
    (net (code "60") (name "Net-(U3-PROG)") (class "Default")
      (node (ref "R8") (pin "1") (pinfunction "1_1") (pintype "passive"))
      (node (ref "U3") (pin "5") (pinfunction "PROG_5") (pintype "input"))
    )
    (net (code "61") (name "Net-(U3-STAT)") (class "Default")
      (node (ref "R2") (pin "2") (pinfunction "2_2") (pintype "passive"))
      (node (ref "U3") (pin "1") (pinfunction "STAT_1") (pintype "output"))
    )
    (net (code "62") (name "VBAT") (class "Default")
      (node (ref "C3") (pin "1") (pinfunction "1_1") (pintype "passive"))
      (node (ref "JP3") (pin "1") (pinfunction "1_1") (pintype "passive"))
      (node (ref "Q3") (pin "3") (pinfunction "D_3") (pintype "passive"))
      (node (ref "R9") (pin "8") (pinfunction "2_8") (pintype "passive"))
      (node (ref "U3") (pin "3") (pinfunction "VBAT_3") (pintype "power_in"))
      (node (ref "X1") (pin "2") (pinfunction "2_2") (pintype "passive"))
    )
    (net (code "63") (name "VBUS") (class "Default")
      (node (ref "CHG") (pin "A") (pinfunction "A_A") (pintype "passive"))
      (node (ref "D4") (pin "A") (pinfunction "A_A") (pintype "passive"))
      (node (ref "JP3") (pin "3") (pinfunction "3_3") (pintype "passive"))
      (node (ref "Q3") (pin "1") (pinfunction "G_1") (pintype "passive"))
      (node (ref "R9") (pin "6") (pinfunction "2_6") (pintype "passive"))
      (node (ref "U3") (pin "4") (pinfunction "VDD_4") (pintype "power_in"))
      (node (ref "X6") (pin "A4B9") (pinfunction "VBUS_A4B9") (pintype "power_in"))
      (node (ref "X6") (pin "B4A9") (pinfunction "VBUS_B4A9") (pintype "power_in"))
    )
    (net (code "64") (name "unconnected-(LED1-DO-Pad3)") (class "Default")
      (node (ref "LED1") (pin "3") (pinfunction "DO_3") (pintype "output"))
    )
    (net (code "65") (name "unconnected-(U$14A-PA15{slash}I15{slash}SERCOM2+4.3-Pad32)") (class "Default")
      (node (ref "U$14") (pin "32") (pinfunction "PA15/I15/SERCOM2+4.3_32") (pintype "bidirectional"))
    )
    (net (code "66") (name "unconnected-(U$14A-PA27{slash}I11-Pad51)") (class "Default")
      (node (ref "U$14") (pin "51") (pinfunction "PA27/I11_51") (pintype "bidirectional"))
    )
    (net (code "67") (name "unconnected-(U$14B-PB01{slash}I1{slash}AIN13{slash}SERCOM5.3-Pad62)") (class "Default")
      (node (ref "U$14") (pin "62") (pinfunction "PB01/I1/AIN13/SERCOM5.3_62") (pintype "bidirectional"))
    )
    (net (code "68") (name "unconnected-(U$14B-PB04{slash}I4{slash}AIN6-Pad5)") (class "Default")
      (node (ref "U$14") (pin "5") (pinfunction "PB04/I4/AIN6_5") (pintype "bidirectional"))
    )
    (net (code "69") (name "unconnected-(U$14B-PB05{slash}I5{slash}AIN7-Pad6)") (class "Default")
      (node (ref "U$14") (pin "6") (pinfunction "PB05/I5/AIN7_6") (pintype "bidirectional"))
    )
    (net (code "70") (name "unconnected-(U$14B-PB06{slash}I6{slash}AIN8-Pad9)") (class "Default")
      (node (ref "U$14") (pin "9") (pinfunction "PB06/I6/AIN8_9") (pintype "bidirectional"))
    )
    (net (code "71") (name "unconnected-(U$14B-PB07{slash}I7{slash}AIN9-Pad10)") (class "Default")
      (node (ref "U$14") (pin "10") (pinfunction "PB07/I7/AIN9_10") (pintype "bidirectional"))
    )
    (net (code "72") (name "unconnected-(U$14B-PB30{slash}I14{slash}SERCOM5.1{slash}SWO-Pad59)") (class "Default")
      (node (ref "U$14") (pin "59") (pinfunction "PB30/I14/SERCOM5.1/SWO_59") (pintype "bidirectional"))
    )
    (net (code "73") (name "unconnected-(U$14B-PB31{slash}I15{slash}SERCOM5.0-Pad60)") (class "Default")
      (node (ref "U$14") (pin "60") (pinfunction "PB31/I15/SERCOM5.0_60") (pintype "bidirectional"))
    )
    (net (code "74") (name "unconnected-(U2-P4-Pad4)") (class "Default")
      (node (ref "U2") (pin "4") (pinfunction "P4_4") (pintype "bidirectional"))
    )
    (net (code "75") (name "unconnected-(X6-SBU1-PadA8)") (class "Default")
      (node (ref "X6") (pin "A8") (pinfunction "SBU1_A8") (pintype "bidirectional"))
    )
    (net (code "76") (name "unconnected-(X6-SBU2-PadB8)") (class "Default")
      (node (ref "X6") (pin "B8") (pinfunction "SBU2_B8") (pintype "bidirectional"))
    )
  )
)
